# v1_0.net
KiCad netlist of a schematic drawn in Altium Designer
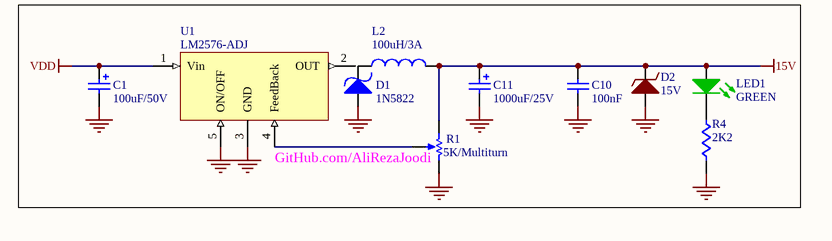
[diagram p0: v1.0.SchDoc]

(export (version "E")
  (design (tool "Eeschema 10.0.6"))
  (components
    (comp (ref "C1")
      (value "100uF/50V")
      (footprint "CAPPR3.05-3.81x6.35")
      (description "Polarized Capacitor (Radial)")
      (fields (field (name "MANUFACTURER") "Generic Components") (field (name "PUBLISHER") "Altium Limited"))
      (libsource (lib "Miscellaneous Devices") (part "Cap Pol1"))
    )
    (comp (ref "C10")
      (value "100nF")
      (footprint "CAPNTO2.54-3.05x1.78A")
      (description "Capacitor")
      (fields
        (field (name "MANUFACTURER") "Generic Components")
        (field (name "Comment") "Cap")
        (field (name "PUBLISHER") "Altium Limited")
      )
      (libsource (lib "Miscellaneous Devices") (part "Cap"))
    )
    (comp (ref "C11")
      (value "1000uF/25V")
      (footprint "CAPPR5-10x12.5")
      (description "Polarized Capacitor (Radial)")
      (fields (field (name "MANUFACTURER") "Generic Components") (field (name "PUBLISHER") "Altium Limited"))
      (libsource (lib "Miscellaneous Devices") (part "Cap Pol1"))
    )
    (comp (ref "D1")
      (value "Diode_SCHOTTKY")
      (footprint "DIODE-0.7")
      (description "Diode")
      (fields
        (field (name "MANUFACTURER") "Generic Components")
        (field (name "DEVICE") "1N5822")
        (field (name "PUBLISHER") "Altium Limited")
      )
      (libsource (lib "my Libraries") (part "Diode_SCHOTTKY"))
    )
    (comp (ref "D2")
      (value "15V")
      (footprint "D_THD_AXIAL0.3_DO-35")
      (description "Diode, Zener")
      (libsource (lib "General") (part "Diode_Zener"))
    )
    (comp (ref "L2")
      (value "100uH/3A")
      (footprint "INDUCTOR-2V")
      (description "Inductor")
      (fields (field (name "MANUFACTURER") "Generic Components") (field (name "PUBLISHER") "Altium Limited"))
      (libsource (lib "my Libraries") (part "Inductor"))
    )
    (comp (ref "LED1")
      (value "GREEN")
      (footprint "LED_THD_5MM_GREEN")
      (description "LED, Green")
      (fields (field (name "MANUFACTURER") "Generic Components") (field (name "PUBLISHER") "Altium Limited"))
      (libsource (lib "Display") (part "LED_GREEN"))
    )
    (comp (ref "R1")
      (value "5K/Multiturn")
      (footprint "VR4_")
      (description "Potentiometer")
      (fields (field (name "MANUFACTURER") "Generic Components") (field (name "PUBLISHER") "Altium Limited"))
      (libsource (lib "my Libraries") (part "RPot1"))
    )
    (comp (ref "R4")
      (value "2K2")
      (footprint "AXIAL-0.4")
      (description "Resistor")
      (fields
        (field (name "MANUFACTURER") "Generic Components")
        (field (name "Comment") "Res1")
        (field (name "PUBLISHER") "Altium Limited")
      )
      (libsource (lib "Miscellaneous Devices") (part "Res1"))
    )
    (comp (ref "U1")
      (value "LM2576-ADJ")
      (footprint "TO220-5H")
      (description "Step-Down Voltage  Regulator")
      (libsource (lib "IC") (part "VoltageRegulator_Switching_StepDown"))
    )
  )
  (nets
    (net (code "1") (name "15V") (class "Default")
      (node (ref "C10") (pin "2") (pinfunction "2_2") (pintype "passive"))
      (node (ref "C11") (pin "1") (pinfunction "1_1") (pintype "passive"))
      (node (ref "D2") (pin "2") (pinfunction "2_2") (pintype "passive"))
      (node (ref "L2") (pin "2") (pinfunction "2_2") (pintype "passive"))
      (node (ref "LED1") (pin "1") (pinfunction "A_1") (pintype "passive"))
      (node (ref "R1") (pin "2") (pinfunction "BOT_2") (pintype "passive"))
    )
    (net (code "2") (name "GND") (class "Default")
      (node (ref "C1") (pin "2") (pinfunction "2_2") (pintype "passive"))
      (node (ref "C10") (pin "1") (pinfunction "1_1") (pintype "passive"))
      (node (ref "C11") (pin "2") (pinfunction "2_2") (pintype "passive"))
      (node (ref "D1") (pin "1") (pinfunction "A_1") (pintype "passive"))
      (node (ref "D2") (pin "1") (pinfunction "1_1") (pintype "passive"))
      (node (ref "R1") (pin "1") (pinfunction "TOP_1") (pintype "passive"))
      (node (ref "R4") (pin "2") (pinfunction "2_2") (pintype "passive"))
      (node (ref "U1") (pin "3") (pinfunction "GND_3") (pintype "power_in"))
      (node (ref "U1") (pin "5") (pinfunction "ON/OFF_5") (pintype "input"))
    )
    (net (code "3") (name "Net-(D1-K)") (class "Default")
      (node (ref "D1") (pin "2") (pinfunction "K_2") (pintype "passive"))
      (node (ref "L2") (pin "1") (pinfunction "1_1") (pintype "passive"))
    )
    (net (code "4") (name "Net-(LED1-K)") (class "Default")
      (node (ref "LED1") (pin "2") (pinfunction "K_2") (pintype "passive"))
      (node (ref "R4") (pin "1") (pinfunction "1_1") (pintype "passive"))
    )
    (net (code "5") (name "Net-(R1-TAP)") (class "Default")
      (node (ref "R1") (pin "3") (pinfunction "TAP_3") (pintype "passive"))
      (node (ref "U1") (pin "4") (pinfunction "FeedBack_4") (pintype "input"))
    )
    (net (code "6") (name "VDD") (class "Default")
      (node (ref "C1") (pin "1") (pinfunction "1_1") (pintype "passive"))
      (node (ref "U1") (pin "1") (pinfunction "Vin_1") (pintype "input"))
    )
    (net (code "7") (name "unconnected-(U1-OUT-Pad2)") (class "Default")
      (node (ref "U1") (pin "2") (pinfunction "OUT_2") (pintype "output"))
    )
  )
)
